# ProProject__CW32__2024-03-03.net
KiCad netlist of a schematic drawn in EasyEDA Pro
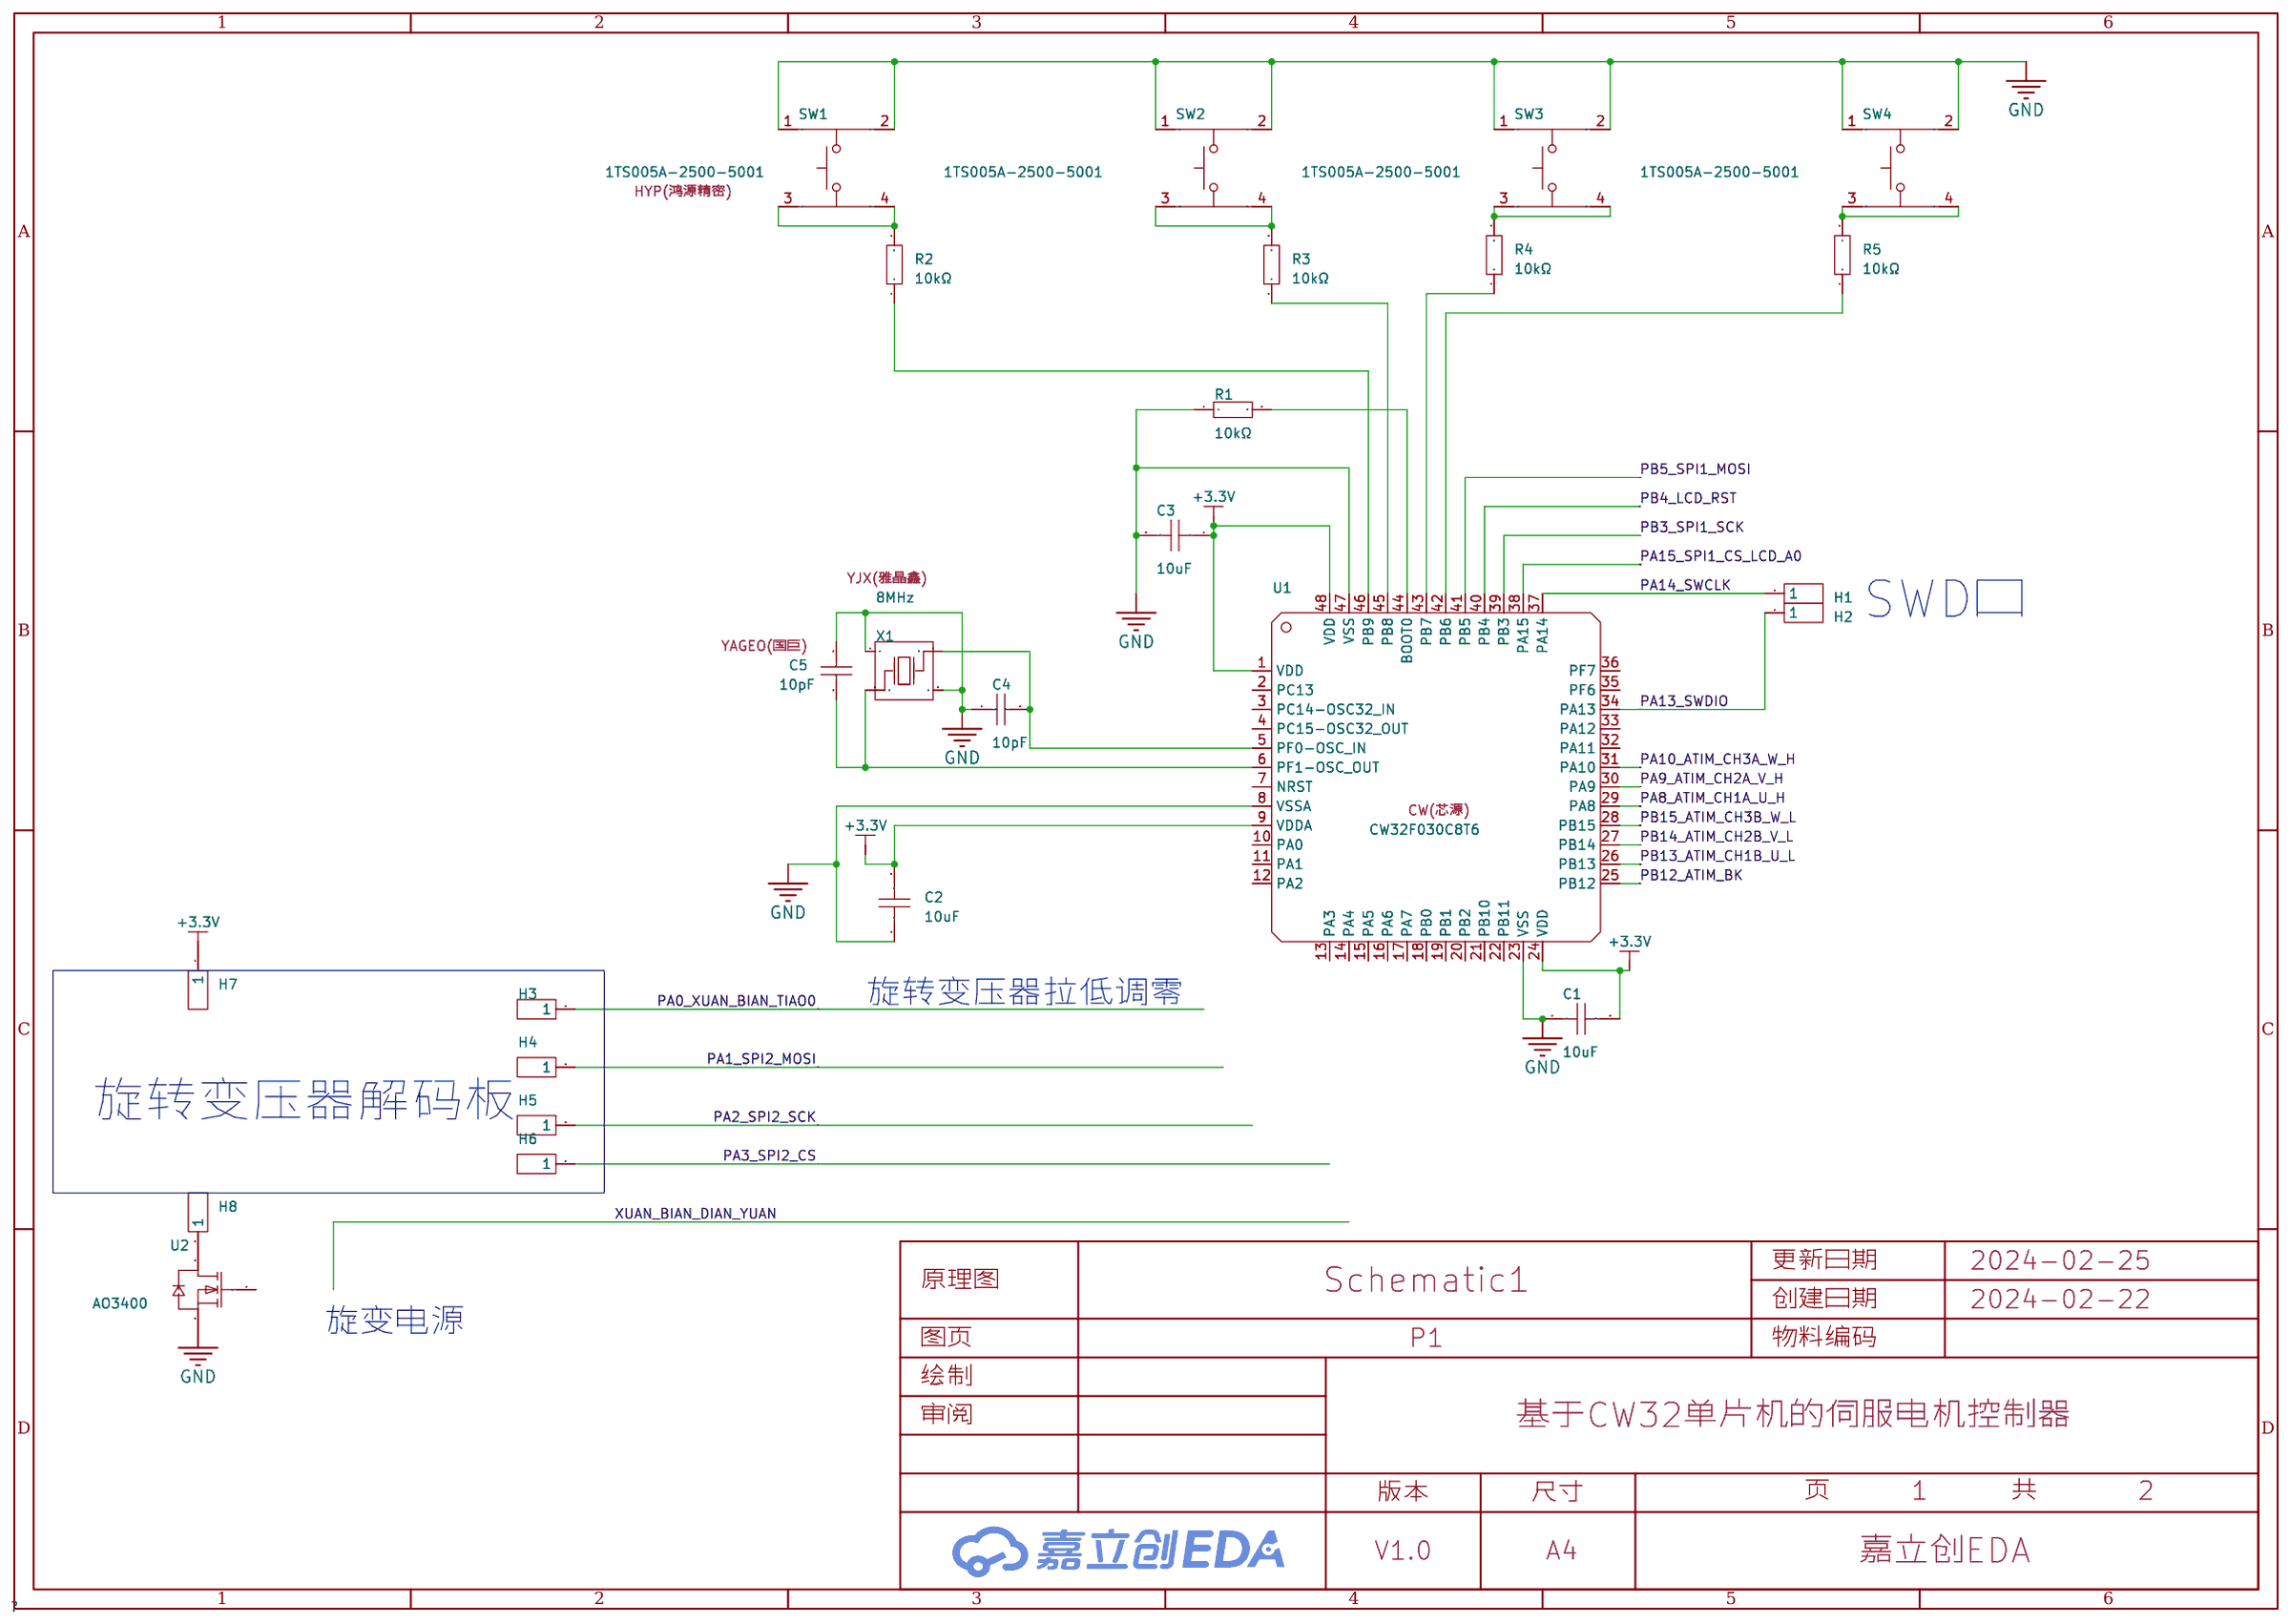
[diagram p0: P1]
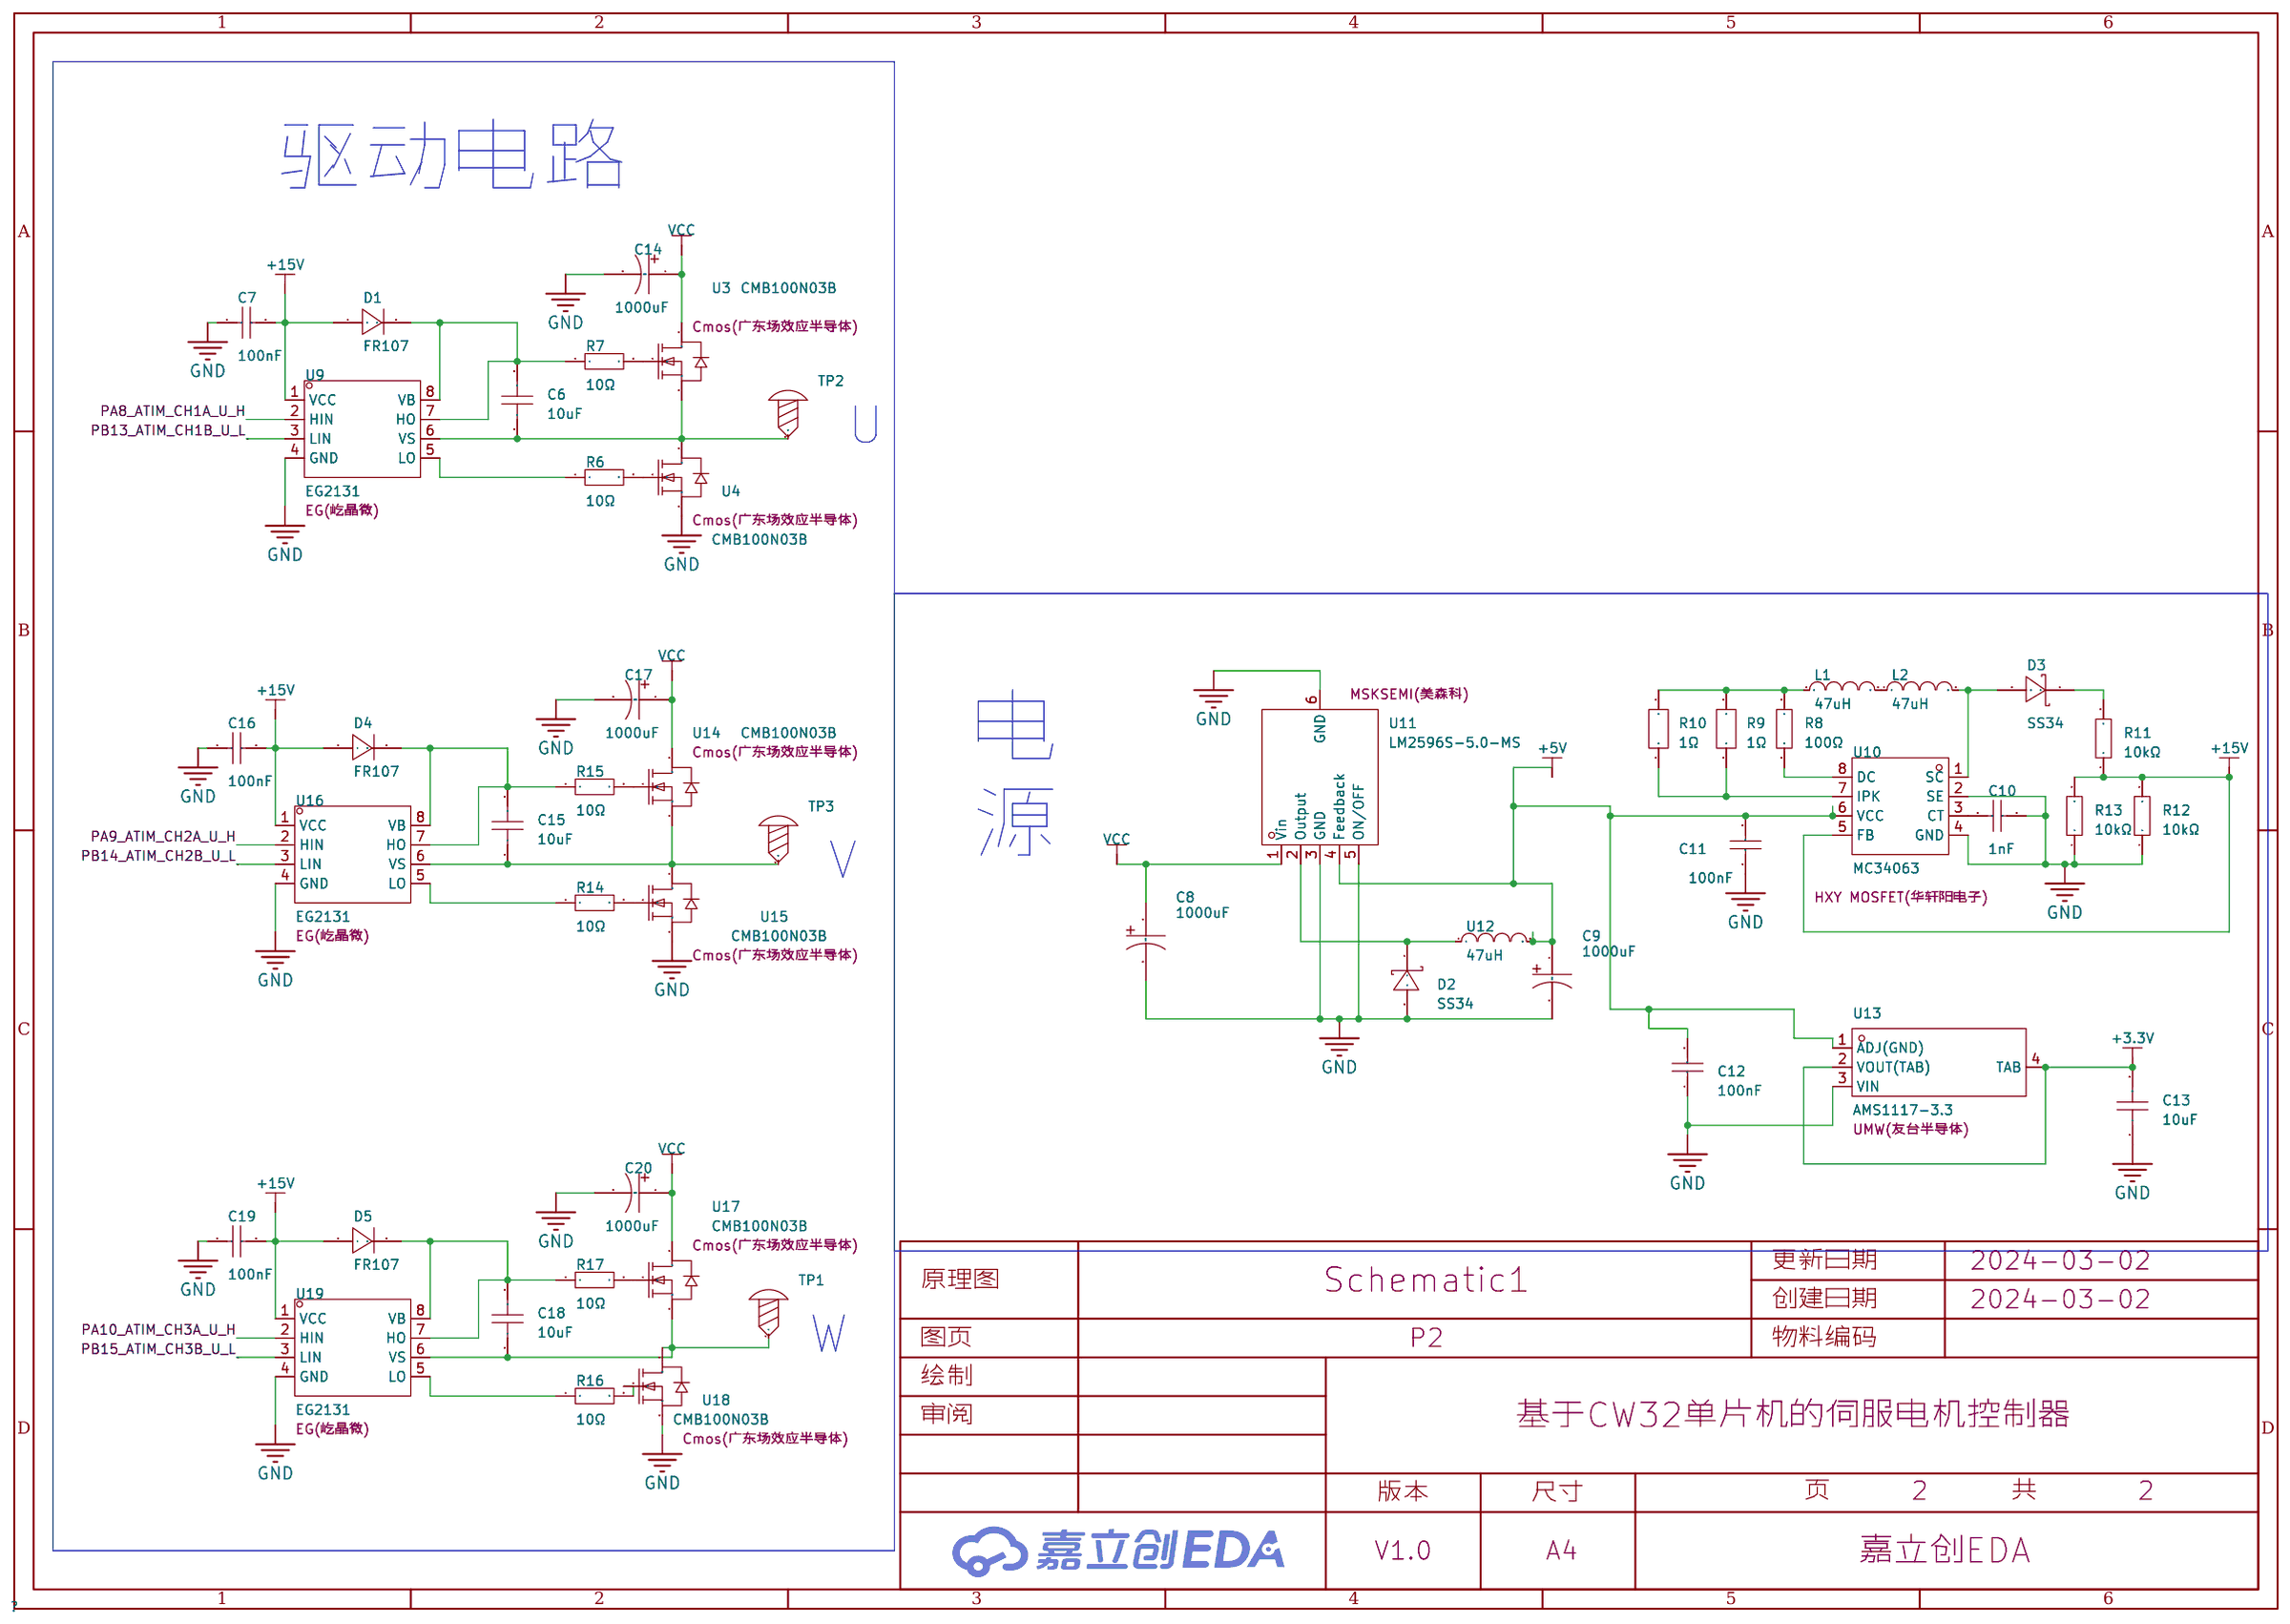
[diagram p1: P2]

(export (version "E")
  (design (tool "Eeschema 10.0.6"))
  (components
    (comp (ref "C1")
      (value "10uF")
      (footprint "easyedapro:C0603")
      (description "容值:10uF;精度:±10%;额定电压:10V;材质(温度系数):X5R;")
      (fields
        (field (name "Manufacturer Part") "CL10A106KP8NNNC")
        (field (name "Manufacturer") "SAMSUNG(三星)")
      )
      (libsource (lib "easyedapro") (part "CL10A106KP8NNNC"))
    )
    (comp (ref "C2")
      (value "10uF")
      (footprint "easyedapro:C0603")
      (description "容值:10uF;精度:±10%;额定电压:10V;材质(温度系数):X5R;")
      (fields
        (field (name "Manufacturer Part") "CL10A106KP8NNNC")
        (field (name "Manufacturer") "SAMSUNG(三星)")
      )
      (libsource (lib "easyedapro") (part "CL10A106KP8NNNC"))
    )
    (comp (ref "C3")
      (value "10uF")
      (footprint "easyedapro:C0603")
      (description "容值:10uF;精度:±10%;额定电压:10V;材质(温度系数):X5R;")
      (fields
        (field (name "Manufacturer Part") "CL10A106KP8NNNC")
        (field (name "Manufacturer") "SAMSUNG(三星)")
      )
      (libsource (lib "easyedapro") (part "CL10A106KP8NNNC"))
    )
    (comp (ref "C4")
      (value "10pF")
      (footprint "easyedapro:C0603")
      (description "容值:10pF;精度:±5%;额定电压:50V;材质(温度系数):NP0;")
      (fields
        (field (name "Manufacturer Part") "CC0603JRNPO9BN100")
        (field (name "Manufacturer") "YAGEO(国巨)")
      )
      (libsource (lib "easyedapro") (part "CC0603JRNPO9BN100"))
    )
    (comp (ref "C5")
      (value "10pF")
      (footprint "easyedapro:C0603")
      (description "容值:10pF;精度:±5%;额定电压:50V;材质(温度系数):NP0;")
      (fields
        (field (name "Manufacturer Part") "CC0603JRNPO9BN100")
        (field (name "Manufacturer") "YAGEO(国巨)")
      )
      (libsource (lib "easyedapro") (part "CC0603JRNPO9BN100"))
    )
    (comp (ref "H1")
      (value "~")
      (footprint "easyedapro:HDR-TH_1P-V-M_XKB_X4611WV-01I-C28D40")
      (libsource (lib "easyedapro") (part "HDR_1x1"))
    )
    (comp (ref "H2")
      (value "~")
      (footprint "easyedapro:HDR-TH_1P-V-M_XKB_X4611WV-01I-C28D40")
      (libsource (lib "easyedapro") (part "HDR_1x1"))
    )
    (comp (ref "H3")
      (value "~")
      (footprint "easyedapro:HDR-TH_1P-V-M_XKB_X4611WV-01I-C28D40")
      (libsource (lib "easyedapro") (part "HDR_1x1"))
    )
    (comp (ref "H4")
      (value "~")
      (footprint "easyedapro:HDR-TH_1P-V-M_XKB_X4611WV-01I-C28D40")
      (libsource (lib "easyedapro") (part "HDR_1x1"))
    )
    (comp (ref "H5")
      (value "~")
      (footprint "easyedapro:HDR-TH_1P-V-M_XKB_X4611WV-01I-C28D40")
      (libsource (lib "easyedapro") (part "HDR_1x1"))
    )
    (comp (ref "H6")
      (value "~")
      (footprint "easyedapro:HDR-TH_1P-V-M_XKB_X4611WV-01I-C28D40")
      (libsource (lib "easyedapro") (part "HDR_1x1"))
    )
    (comp (ref "H7")
      (value "~")
      (footprint "easyedapro:HDR-TH_1P-V-M_XKB_X4611WV-01I-C28D40")
      (libsource (lib "easyedapro") (part "HDR_1x1"))
    )
    (comp (ref "H8")
      (value "~")
      (footprint "easyedapro:HDR-TH_1P-V-M_XKB_X4611WV-01I-C28D40")
      (libsource (lib "easyedapro") (part "HDR_1x1"))
    )
    (comp (ref "R1")
      (value "10kΩ")
      (footprint "easyedapro:R0603")
      (description "电阻类型:厚膜电阻;阻值:10kΩ;精度:±1%;功率:100mW;最大工作电压:75V;温度系数:±100ppm/°C;")
      (fields (field (name "Manufacturer Part") "RC0603FR-0710KL") (field (name "Manufacturer") "YAGEO(国巨)"))
      (libsource (lib "easyedapro") (part "RC0603FR-0710KL"))
    )
    (comp (ref "R2")
      (value "10kΩ")
      (footprint "easyedapro:R0603")
      (description "电阻类型:厚膜电阻;阻值:10kΩ;精度:±1%;功率:100mW;最大工作电压:75V;温度系数:±100ppm/°C;")
      (fields (field (name "Manufacturer Part") "RC0603FR-0710KL") (field (name "Manufacturer") "YAGEO(国巨)"))
      (libsource (lib "easyedapro") (part "RC0603FR-0710KL"))
    )
    (comp (ref "R3")
      (value "10kΩ")
      (footprint "easyedapro:R0603")
      (description "电阻类型:厚膜电阻;阻值:10kΩ;精度:±1%;功率:100mW;最大工作电压:75V;温度系数:±100ppm/°C;")
      (fields (field (name "Manufacturer Part") "RC0603FR-0710KL") (field (name "Manufacturer") "YAGEO(国巨)"))
      (libsource (lib "easyedapro") (part "RC0603FR-0710KL"))
    )
    (comp (ref "R4")
      (value "10kΩ")
      (footprint "easyedapro:R0603")
      (description "电阻类型:厚膜电阻;阻值:10kΩ;精度:±1%;功率:100mW;最大工作电压:75V;温度系数:±100ppm/°C;")
      (fields (field (name "Manufacturer Part") "RC0603FR-0710KL") (field (name "Manufacturer") "YAGEO(国巨)"))
      (libsource (lib "easyedapro") (part "RC0603FR-0710KL"))
    )
    (comp (ref "R5")
      (value "10kΩ")
      (footprint "easyedapro:R0603")
      (description "电阻类型:厚膜电阻;阻值:10kΩ;精度:±1%;功率:100mW;最大工作电压:75V;温度系数:±100ppm/°C;")
      (fields (field (name "Manufacturer Part") "RC0603FR-0710KL") (field (name "Manufacturer") "YAGEO(国巨)"))
      (libsource (lib "easyedapro") (part "RC0603FR-0710KL"))
    )
    (comp (ref "SW1")
      (value "1TS005A-2500-5001")
      (footprint "easyedapro:SW-TH_4P-L6.0-W6.0-P3.90-LS6.5")
      (fields (field (name "Manufacturer") "HYP(鸿源精密)"))
      (libsource (lib "easyedapro") (part "1TS005A-2500-5001"))
    )
    (comp (ref "SW2")
      (value "1TS005A-2500-5001")
      (footprint "easyedapro:SW-TH_4P-L6.0-W6.0-P3.90-LS6.5")
      (fields (field (name "Manufacturer") "HYP(鸿源精密)"))
      (libsource (lib "easyedapro") (part "1TS005A-2500-5001"))
    )
    (comp (ref "SW3")
      (value "1TS005A-2500-5001")
      (footprint "easyedapro:SW-TH_4P-L6.0-W6.0-P3.90-LS6.5")
      (fields (field (name "Manufacturer") "HYP(鸿源精密)"))
      (libsource (lib "easyedapro") (part "1TS005A-2500-5001"))
    )
    (comp (ref "SW4")
      (value "1TS005A-2500-5001")
      (footprint "easyedapro:SW-TH_4P-L6.0-W6.0-P3.90-LS6.5")
      (fields (field (name "Manufacturer") "HYP(鸿源精密)"))
      (libsource (lib "easyedapro") (part "1TS005A-2500-5001"))
    )
    (comp (ref "U1")
      (value "CW32F030C8T6")
      (footprint "easyedapro:LQFP-48_L7.0-W7.0-P0.50-LS9.0-TL")
      (description "CPU内核:ARM-M系列;RAM总容量:8KB;GPIO端口数量:39;工作电压范围:1.65V~5.5V;CPU最大主频:64MHz;程序存储器类型:-;")
      (fields (field (name "Manufacturer") "CW(芯源)"))
      (libsource (lib "easyedapro") (part "CW32F030C8T6_C3019113"))
    )
    (comp (ref "U2")
      (value "AO3400")
      (footprint "easyedapro:SOT-23-3_L2.9-W1.3-P0.95-LS2.4-BR")
      (fields (field (name "Manufacturer") "ElecSuper(静芯微)"))
      (libsource (lib "easyedapro") (part "AO3400_C5224189"))
    )
    (comp (ref "X1")
      (value "8MHz")
      (footprint "easyedapro:OSC-SMD_4P-L3.2-W2.5-BL")
      (description "晶振类型:贴片晶振;频率:8MHz;常温频差:±10ppm;外接负载电容:10pF;频率稳定度(全温):±15ppm;")
      (fields (field (name "Manufacturer Part") "TAXM8M4RDBCCT2T") (field (name "Manufacturer") "YJX(雅晶鑫)"))
      (libsource (lib "easyedapro") (part "TAXM8M4RDBCCT2T"))
    )
    (comp (ref "C6")
      (value "10uF")
      (footprint "easyedapro:C0805")
      (description "容值:10uF;精度:±10%;额定电压:25V;材质(温度系数):X5R;")
      (fields
        (field (name "Manufacturer Part") "CL21A106KAYNNNE")
        (field (name "Manufacturer") "SAMSUNG(三星)")
      )
      (libsource (lib "easyedapro") (part "CL21A106KAYNNNE"))
    )
    (comp (ref "C7")
      (value "100nF")
      (footprint "easyedapro:C0603")
      (description "容值:100nF;精度:±10%;额定电压:50V;材质(温度系数):X7R;")
      (fields (field (name "Manufacturer Part") "0603B104K500NT") (field (name "Manufacturer") "FH(风华)"))
      (libsource (lib "easyedapro") (part "0603B104K500NT"))
    )
    (comp (ref "C8")
      (value "1000uF")
      (footprint "easyedapro:CAP-TH_BD10.0-P5.00-D1.0-FD")
      (description "容值:1000uF;精度:±20%;额定电压:35V;")
      (fields (field (name "Manufacturer Part") "ERR1VM102G20OT") (field (name "Manufacturer") "AISHI(艾华集团)"))
      (libsource (lib "easyedapro") (part "ERR1VM102G20OT"))
    )
    (comp (ref "C9")
      (value "1000uF")
      (footprint "easyedapro:CAP-TH_BD10.0-P5.00-D1.0-FD")
      (description "容值:1000uF;精度:±20%;额定电压:35V;")
      (fields (field (name "Manufacturer Part") "ERR1VM102G20OT") (field (name "Manufacturer") "AISHI(艾华集团)"))
      (libsource (lib "easyedapro") (part "ERR1VM102G20OT"))
    )
    (comp (ref "C10")
      (value "1nF")
      (footprint "easyedapro:C0603")
      (description "容值:1nF;精度:±5%;额定电压:50V;材质(温度系数):NP0;")
      (fields
        (field (name "Manufacturer Part") "CC0603JRNPO9BN102")
        (field (name "Manufacturer") "YAGEO(国巨)")
      )
      (libsource (lib "easyedapro") (part "CC0603JRNPO9BN102"))
    )
    (comp (ref "C11")
      (value "100nF")
      (footprint "easyedapro:C0603")
      (description "容值:100nF;精度:±10%;额定电压:50V;材质(温度系数):X7R;")
      (fields (field (name "Manufacturer Part") "0603B104K500NT") (field (name "Manufacturer") "FH(风华)"))
      (libsource (lib "easyedapro") (part "0603B104K500NT"))
    )
    (comp (ref "C12")
      (value "100nF")
      (footprint "easyedapro:C0603")
      (description "容值:100nF;精度:±10%;额定电压:50V;材质(温度系数):X7R;")
      (fields (field (name "Manufacturer Part") "0603B104K500NT") (field (name "Manufacturer") "FH(风华)"))
      (libsource (lib "easyedapro") (part "0603B104K500NT"))
    )
    (comp (ref "C13")
      (value "10uF")
      (footprint "easyedapro:C0603")
      (description "容值:10uF;精度:±10%;额定电压:10V;材质(温度系数):X5R;")
      (fields
        (field (name "Manufacturer Part") "CL10A106KP8NNNC")
        (field (name "Manufacturer") "SAMSUNG(三星)")
      )
      (libsource (lib "easyedapro") (part "CL10A106KP8NNNC"))
    )
    (comp (ref "C14")
      (value "1000uF")
      (footprint "easyedapro:CAP-TH_BD10.0-P5.00-D1.0-FD")
      (description "容值:1000uF;精度:±20%;额定电压:35V;")
      (fields (field (name "Manufacturer Part") "ERR1VM102G20OT") (field (name "Manufacturer") "AISHI(艾华集团)"))
      (libsource (lib "easyedapro") (part "ERR1VM102G20OT"))
    )
    (comp (ref "C15")
      (value "10uF")
      (footprint "easyedapro:C0805")
      (description "容值:10uF;精度:±10%;额定电压:25V;材质(温度系数):X5R;")
      (fields
        (field (name "Manufacturer Part") "CL21A106KAYNNNE")
        (field (name "Manufacturer") "SAMSUNG(三星)")
      )
      (libsource (lib "easyedapro") (part "CL21A106KAYNNNE"))
    )
    (comp (ref "C16")
      (value "100nF")
      (footprint "easyedapro:C0603")
      (description "容值:100nF;精度:±10%;额定电压:50V;材质(温度系数):X7R;")
      (fields (field (name "Manufacturer Part") "0603B104K500NT") (field (name "Manufacturer") "FH(风华)"))
      (libsource (lib "easyedapro") (part "0603B104K500NT"))
    )
    (comp (ref "C17")
      (value "1000uF")
      (footprint "easyedapro:CAP-TH_BD10.0-P5.00-D1.0-FD")
      (description "容值:1000uF;精度:±20%;额定电压:35V;")
      (fields (field (name "Manufacturer Part") "ERR1VM102G20OT") (field (name "Manufacturer") "AISHI(艾华集团)"))
      (libsource (lib "easyedapro") (part "ERR1VM102G20OT"))
    )
    (comp (ref "C18")
      (value "10uF")
      (footprint "easyedapro:C0805")
      (description "容值:10uF;精度:±10%;额定电压:25V;材质(温度系数):X5R;")
      (fields
        (field (name "Manufacturer Part") "CL21A106KAYNNNE")
        (field (name "Manufacturer") "SAMSUNG(三星)")
      )
      (libsource (lib "easyedapro") (part "CL21A106KAYNNNE"))
    )
    (comp (ref "C19")
      (value "100nF")
      (footprint "easyedapro:C0603")
      (description "容值:100nF;精度:±10%;额定电压:50V;材质(温度系数):X7R;")
      (fields (field (name "Manufacturer Part") "0603B104K500NT") (field (name "Manufacturer") "FH(风华)"))
      (libsource (lib "easyedapro") (part "0603B104K500NT"))
    )
    (comp (ref "C20")
      (value "1000uF")
      (footprint "easyedapro:CAP-TH_BD10.0-P5.00-D1.0-FD")
      (description "容值:1000uF;精度:±20%;额定电压:35V;")
      (fields (field (name "Manufacturer Part") "ERR1VM102G20OT") (field (name "Manufacturer") "AISHI(艾华集团)"))
      (libsource (lib "easyedapro") (part "ERR1VM102G20OT"))
    )
    (comp (ref "D1")
      (value "FR107")
      (footprint "easyedapro:DO-41_BD2.4-L4.7-P8.70-D0.9-FD")
      (description "二极管配置:-;正向压降(Vf):1.3V@1A;直流反向耐压(Vr):1kV;平均整流电流(Io):1A;反向恢复时间(trr):500ns;")
      (fields (field (name "Manufacturer") "MDD"))
      (libsource (lib "easyedapro") (part "FR107_C35253"))
    )
    (comp (ref "D2")
      (value "SS34")
      (footprint "easyedapro:SMA_L4.3-W2.6-LS5.2-RD")
      (description "二极管配置:独立式;正向压降(Vf):550mV@3A;直流反向耐压(Vr):40V;平均整流电流(Io):3A;")
      (fields (field (name "Manufacturer") "MDD"))
      (libsource (lib "easyedapro") (part "SS34_C8678"))
    )
    (comp (ref "D3")
      (value "SS34")
      (footprint "easyedapro:SMA_L4.3-W2.6-LS5.2-RD")
      (description "二极管配置:独立式;正向压降(Vf):550mV@3A;直流反向耐压(Vr):40V;平均整流电流(Io):3A;")
      (fields (field (name "Manufacturer") "MDD"))
      (libsource (lib "easyedapro") (part "SS34_C8678"))
    )
    (comp (ref "D4")
      (value "FR107")
      (footprint "easyedapro:DO-41_BD2.4-L4.7-P8.70-D0.9-FD")
      (description "二极管配置:-;正向压降(Vf):1.3V@1A;直流反向耐压(Vr):1kV;平均整流电流(Io):1A;反向恢复时间(trr):500ns;")
      (fields (field (name "Manufacturer") "MDD"))
      (libsource (lib "easyedapro") (part "FR107_C35253"))
    )
    (comp (ref "D5")
      (value "FR107")
      (footprint "easyedapro:DO-41_BD2.4-L4.7-P8.70-D0.9-FD")
      (description "二极管配置:-;正向压降(Vf):1.3V@1A;直流反向耐压(Vr):1kV;平均整流电流(Io):1A;反向恢复时间(trr):500ns;")
      (fields (field (name "Manufacturer") "MDD"))
      (libsource (lib "easyedapro") (part "FR107_C35253"))
    )
    (comp (ref "L1")
      (value "47uH")
      (footprint "easyedapro:IND-SMD_L4.5-W4.0_SLF0403")
      (description "电感值:47uH;精度:±10%;额定电流:540mA;")
      (fields
        (field (name "Manufacturer Part") "SLF0403-470KTT")
        (field (name "Manufacturer") "Sunltech(韩国顺磁)")
      )
      (libsource (lib "easyedapro") (part "SLF0403-470KTT"))
    )
    (comp (ref "L2")
      (value "47uH")
      (footprint "easyedapro:IND-SMD_L4.5-W4.0_SLF0403")
      (description "电感值:47uH;精度:±10%;额定电流:540mA;")
      (fields
        (field (name "Manufacturer Part") "SLF0403-470KTT")
        (field (name "Manufacturer") "Sunltech(韩国顺磁)")
      )
      (libsource (lib "easyedapro") (part "SLF0403-470KTT"))
    )
    (comp (ref "R6")
      (value "10Ω")
      (footprint "easyedapro:R0603")
      (description "电阻类型:厚膜电阻;阻值:10Ω;精度:±1%;功率:100mW;最大工作电压:75V;温度系数:±400ppm/°C;")
      (fields
        (field (name "Manufacturer Part") "0603WAF100JT5E")
        (field (name "Manufacturer") "UNI-ROYAL(厚声)")
      )
      (libsource (lib "easyedapro") (part "0603WAF100JT5E"))
    )
    (comp (ref "R7")
      (value "10Ω")
      (footprint "easyedapro:R0603")
      (description "电阻类型:厚膜电阻;阻值:10Ω;精度:±1%;功率:100mW;最大工作电压:75V;温度系数:±400ppm/°C;")
      (fields
        (field (name "Manufacturer Part") "0603WAF100JT5E")
        (field (name "Manufacturer") "UNI-ROYAL(厚声)")
      )
      (libsource (lib "easyedapro") (part "0603WAF100JT5E"))
    )
    (comp (ref "R8")
      (value "100Ω")
      (footprint "easyedapro:R0603")
      (description "电阻类型:厚膜电阻;阻值:100Ω;精度:±1%;功率:100mW;最大工作电压:75V;温度系数:±100ppm/°C;")
      (fields (field (name "Manufacturer Part") "RC0603FR-07100RL") (field (name "Manufacturer") "YAGEO(国巨)"))
      (libsource (lib "easyedapro") (part "RC0603FR-07100RL"))
    )
    (comp (ref "R9")
      (value "1Ω")
      (footprint "easyedapro:R0603")
      (description "电阻类型:厚膜电阻;阻值:1Ω;精度:±1%;功率:100mW;最大工作电压:75V;")
      (fields (field (name "Manufacturer Part") "SCR0603F1R") (field (name "Manufacturer") "VO(翔胜)"))
      (libsource (lib "easyedapro") (part "SCR0603F1R"))
    )
    (comp (ref "R10")
      (value "1Ω")
      (footprint "easyedapro:R0603")
      (description "电阻类型:厚膜电阻;阻值:1Ω;精度:±1%;功率:100mW;最大工作电压:75V;")
      (fields (field (name "Manufacturer Part") "SCR0603F1R") (field (name "Manufacturer") "VO(翔胜)"))
      (libsource (lib "easyedapro") (part "SCR0603F1R"))
    )
    (comp (ref "R11")
      (value "10kΩ")
      (footprint "easyedapro:R0603")
      (description "电阻类型:厚膜电阻;阻值:10kΩ;精度:±1%;功率:100mW;最大工作电压:75V;温度系数:±100ppm/°C;")
      (fields (field (name "Manufacturer Part") "RC0603FR-0710KL") (field (name "Manufacturer") "YAGEO(国巨)"))
      (libsource (lib "easyedapro") (part "RC0603FR-0710KL"))
    )
    (comp (ref "R12")
      (value "10kΩ")
      (footprint "easyedapro:R0603")
      (description "电阻类型:厚膜电阻;阻值:10kΩ;精度:±1%;功率:100mW;最大工作电压:75V;温度系数:±100ppm/°C;")
      (fields (field (name "Manufacturer Part") "RC0603FR-0710KL") (field (name "Manufacturer") "YAGEO(国巨)"))
      (libsource (lib "easyedapro") (part "RC0603FR-0710KL"))
    )
    (comp (ref "R13")
      (value "10kΩ")
      (footprint "easyedapro:R0603")
      (description "电阻类型:厚膜电阻;阻值:10kΩ;精度:±1%;功率:100mW;最大工作电压:75V;温度系数:±100ppm/°C;")
      (fields (field (name "Manufacturer Part") "RC0603FR-0710KL") (field (name "Manufacturer") "YAGEO(国巨)"))
      (libsource (lib "easyedapro") (part "RC0603FR-0710KL"))
    )
    (comp (ref "R14")
      (value "10Ω")
      (footprint "easyedapro:R0603")
      (description "电阻类型:厚膜电阻;阻值:10Ω;精度:±1%;功率:100mW;最大工作电压:75V;温度系数:±400ppm/°C;")
      (fields
        (field (name "Manufacturer Part") "0603WAF100JT5E")
        (field (name "Manufacturer") "UNI-ROYAL(厚声)")
      )
      (libsource (lib "easyedapro") (part "0603WAF100JT5E"))
    )
    (comp (ref "R15")
      (value "10Ω")
      (footprint "easyedapro:R0603")
      (description "电阻类型:厚膜电阻;阻值:10Ω;精度:±1%;功率:100mW;最大工作电压:75V;温度系数:±400ppm/°C;")
      (fields
        (field (name "Manufacturer Part") "0603WAF100JT5E")
        (field (name "Manufacturer") "UNI-ROYAL(厚声)")
      )
      (libsource (lib "easyedapro") (part "0603WAF100JT5E"))
    )
    (comp (ref "R16")
      (value "10Ω")
      (footprint "easyedapro:R0603")
      (description "电阻类型:厚膜电阻;阻值:10Ω;精度:±1%;功率:100mW;最大工作电压:75V;温度系数:±400ppm/°C;")
      (fields
        (field (name "Manufacturer Part") "0603WAF100JT5E")
        (field (name "Manufacturer") "UNI-ROYAL(厚声)")
      )
      (libsource (lib "easyedapro") (part "0603WAF100JT5E"))
    )
    (comp (ref "R17")
      (value "10Ω")
      (footprint "easyedapro:R0603")
      (description "电阻类型:厚膜电阻;阻值:10Ω;精度:±1%;功率:100mW;最大工作电压:75V;温度系数:±400ppm/°C;")
      (fields
        (field (name "Manufacturer Part") "0603WAF100JT5E")
        (field (name "Manufacturer") "UNI-ROYAL(厚声)")
      )
      (libsource (lib "easyedapro") (part "0603WAF100JT5E"))
    )
    (comp (ref "TP1") (value "~") (footprint "easyedapro:M4螺丝") (libsource (lib "easyedapro") (part "螺丝孔")))
    (comp (ref "TP2") (value "~") (footprint "easyedapro:M4螺丝") (libsource (lib "easyedapro") (part "螺丝孔")))
    (comp (ref "TP3") (value "~") (footprint "easyedapro:M4螺丝") (libsource (lib "easyedapro") (part "螺丝孔")))
    (comp (ref "U3")
      (value "CMB100N03B")
      (footprint "easyedapro:TO-263-2_L10.1-W9.1-P5.08-LS15.2-BR")
      (description "类型:N沟道;漏源电压(Vdss):30V;连续漏极电流(Id):100A;功率(Pd):300W;导通电阻(RDS(on)@Vgs,Id):4.5mΩ;")
      (fields (field (name "Manufacturer") "Cmos(广东场效应半导体)"))
      (libsource (lib "easyedapro") (part "CMB100N03B"))
    )
    (comp (ref "U4")
      (value "CMB100N03B")
      (footprint "easyedapro:TO-263-2_L10.1-W9.1-P5.08-LS15.2-BR")
      (description "类型:N沟道;漏源电压(Vdss):30V;连续漏极电流(Id):100A;功率(Pd):300W;导通电阻(RDS(on)@Vgs,Id):4.5mΩ;")
      (fields (field (name "Manufacturer") "Cmos(广东场效应半导体)"))
      (libsource (lib "easyedapro") (part "CMB100N03B"))
    )
    (comp (ref "U9")
      (value "EG2131")
      (footprint "easyedapro:SOIC-8_L5.0-W4.0-P1.27-LS6.0-BL")
      (fields (field (name "Manufacturer") "EG(屹晶微)"))
      (libsource (lib "easyedapro") (part "EG2131"))
    )
    (comp (ref "U10")
      (value "MC34063")
      (footprint "easyedapro:SOIC-8_L5.0-W4.0-P1.27-LS6.0-BL")
      (description "功能类型:升降压型;输出类型:可调;输入电压:3V~40V;输出电压:1.25V~40V;输出电流(最大值):1.3A;")
      (fields (field (name "Manufacturer") "HXY MOSFET(华轩阳电子)"))
      (libsource (lib "easyedapro") (part "MC34063_C5349988"))
    )
    (comp (ref "U11")
      (value "LM2596S-5.0-MS")
      (footprint "easyedapro:TO-263-5_L10.0-W8.4-P1.70-LS15.3-BR")
      (description "功能类型:降压型;输出类型:-;输入电压:7V~40V;输出电压:5V;输出电流(最大值):3A;")
      (fields (field (name "Manufacturer") "MSKSEMI(美森科)"))
      (libsource (lib "easyedapro") (part "LM2596S-5.0_C5174628"))
    )
    (comp (ref "U12")
      (value "47uH")
      (footprint "easyedapro:IND-SMD_L7.1-W6.6")
      (description "电感值:47uH;精度:±20%;额定电流:1.25A;饱和电流(Isat):1.66A;类型:一体成型电感;")
      (fields (field (name "Manufacturer Part") "APH0630T470M") (field (name "Manufacturer") "APV(爱普微)"))
      (libsource (lib "easyedapro") (part "APH0630T470M"))
    )
    (comp (ref "U13")
      (value "AMS1117-3.3")
      (footprint "easyedapro:SOT-223-4_L6.5-W3.5-P2.30-LS7.0-BR")
      (description "输出类型:固定;最大输入电压:12V;输出电压:3.3V;最大输出电流:1A;电源纹波抑制比(PSRR):60dB@(120Hz);输出极性:正极;")
      (fields (field (name "Manufacturer") "UMW(友台半导体)"))
      (libsource (lib "easyedapro") (part "AMS1117-3.3_C347222"))
    )
    (comp (ref "U14")
      (value "CMB100N03B")
      (footprint "easyedapro:TO-263-2_L10.1-W9.1-P5.08-LS15.2-BR")
      (description "类型:N沟道;漏源电压(Vdss):30V;连续漏极电流(Id):100A;功率(Pd):300W;导通电阻(RDS(on)@Vgs,Id):4.5mΩ;")
      (fields (field (name "Manufacturer") "Cmos(广东场效应半导体)"))
      (libsource (lib "easyedapro") (part "CMB100N03B"))
    )
    (comp (ref "U15")
      (value "CMB100N03B")
      (footprint "easyedapro:TO-263-2_L10.1-W9.1-P5.08-LS15.2-BR")
      (description "类型:N沟道;漏源电压(Vdss):30V;连续漏极电流(Id):100A;功率(Pd):300W;导通电阻(RDS(on)@Vgs,Id):4.5mΩ;")
      (fields (field (name "Manufacturer") "Cmos(广东场效应半导体)"))
      (libsource (lib "easyedapro") (part "CMB100N03B"))
    )
    (comp (ref "U16")
      (value "EG2131")
      (footprint "easyedapro:SOIC-8_L5.0-W4.0-P1.27-LS6.0-BL")
      (fields (field (name "Manufacturer") "EG(屹晶微)"))
      (libsource (lib "easyedapro") (part "EG2131"))
    )
    (comp (ref "U17")
      (value "CMB100N03B")
      (footprint "easyedapro:TO-263-2_L10.1-W9.1-P5.08-LS15.2-BR")
      (description "类型:N沟道;漏源电压(Vdss):30V;连续漏极电流(Id):100A;功率(Pd):300W;导通电阻(RDS(on)@Vgs,Id):4.5mΩ;")
      (fields (field (name "Manufacturer") "Cmos(广东场效应半导体)"))
      (libsource (lib "easyedapro") (part "CMB100N03B"))
    )
    (comp (ref "U18")
      (value "CMB100N03B")
      (footprint "easyedapro:TO-263-2_L10.1-W9.1-P5.08-LS15.2-BR")
      (description "类型:N沟道;漏源电压(Vdss):30V;连续漏极电流(Id):100A;功率(Pd):300W;导通电阻(RDS(on)@Vgs,Id):4.5mΩ;")
      (fields (field (name "Manufacturer") "Cmos(广东场效应半导体)"))
      (libsource (lib "easyedapro") (part "CMB100N03B"))
    )
    (comp (ref "U19")
      (value "EG2131")
      (footprint "easyedapro:SOIC-8_L5.0-W4.0-P1.27-LS6.0-BL")
      (fields (field (name "Manufacturer") "EG(屹晶微)"))
      (libsource (lib "easyedapro") (part "EG2131"))
    )
  )
  (nets
    (net (code "1") (name "+3.3V") (class "Default")
      (node (ref "C1") (pin "2") (pinfunction "2_2") (pintype "unspecified"))
      (node (ref "C13") (pin "2") (pinfunction "2_2") (pintype "unspecified"))
      (node (ref "C2") (pin "2") (pinfunction "2_2") (pintype "unspecified"))
      (node (ref "C3") (pin "1") (pinfunction "1_1") (pintype "unspecified"))
      (node (ref "H7") (pin "1") (pinfunction "1_1") (pintype "unspecified"))
      (node (ref "U1") (pin "1") (pinfunction "VDD_1") (pintype "unspecified"))
      (node (ref "U1") (pin "24") (pinfunction "VDD_24") (pintype "unspecified"))
      (node (ref "U1") (pin "48") (pinfunction "VDD_48") (pintype "unspecified"))
      (node (ref "U1") (pin "9") (pinfunction "VDDA_9") (pintype "unspecified"))
      (node (ref "U13") (pin "2") (pinfunction "VOUT(TAB)_2") (pintype "unspecified"))
      (node (ref "U13") (pin "4") (pinfunction "TAB_4") (pintype "unspecified"))
    )
    (net (code "2") (name "+5V") (class "Default")
      (node (ref "C11") (pin "2") (pinfunction "2_2") (pintype "input"))
      (node (ref "C12") (pin "2") (pinfunction "2_2") (pintype "input"))
      (node (ref "C9") (pin "1") (pinfunction "1_1") (pintype "input"))
      (node (ref "U10") (pin "6") (pinfunction "VCC_6") (pintype "unspecified"))
      (node (ref "U11") (pin "4") (pinfunction "Feedback_4") (pintype "unspecified"))
      (node (ref "U12") (pin "2") (pinfunction "2_2") (pintype "unspecified"))
      (node (ref "U13") (pin "1") (pinfunction "ADJ(GND)_1") (pintype "unspecified"))
    )
    (net (code "3") (name "+15V") (class "Default")
      (node (ref "C16") (pin "2") (pinfunction "2_2") (pintype "input"))
      (node (ref "C19") (pin "2") (pinfunction "2_2") (pintype "input"))
      (node (ref "C7") (pin "2") (pinfunction "2_2") (pintype "input"))
      (node (ref "D1") (pin "1") (pinfunction "A_1") (pintype "unspecified"))
      (node (ref "D4") (pin "1") (pinfunction "A_1") (pintype "unspecified"))
      (node (ref "D5") (pin "1") (pinfunction "A_1") (pintype "unspecified"))
      (node (ref "R11") (pin "1") (pinfunction "1_1") (pintype "input"))
      (node (ref "R12") (pin "2") (pinfunction "2_2") (pintype "input"))
      (node (ref "R13") (pin "2") (pinfunction "2_2") (pintype "input"))
      (node (ref "U10") (pin "5") (pinfunction "FB_5") (pintype "unspecified"))
      (node (ref "U16") (pin "1") (pinfunction "VCC_1") (pintype "unspecified"))
      (node (ref "U19") (pin "1") (pinfunction "VCC_1") (pintype "unspecified"))
      (node (ref "U9") (pin "1") (pinfunction "VCC_1") (pintype "unspecified"))
    )
    (net (code "4") (name "GND") (class "Default")
      (node (ref "C1") (pin "1") (pinfunction "1_1") (pintype "unspecified"))
      (node (ref "C10") (pin "2") (pinfunction "2_2") (pintype "input"))
      (node (ref "C11") (pin "1") (pinfunction "1_1") (pintype "input"))
      (node (ref "C12") (pin "1") (pinfunction "1_1") (pintype "input"))
      (node (ref "C13") (pin "1") (pinfunction "1_1") (pintype "unspecified"))
      (node (ref "C14") (pin "2") (pinfunction "2_2") (pintype "input"))
      (node (ref "C16") (pin "1") (pinfunction "1_1") (pintype "input"))
      (node (ref "C17") (pin "2") (pinfunction "2_2") (pintype "input"))
      (node (ref "C19") (pin "1") (pinfunction "1_1") (pintype "input"))
      (node (ref "C2") (pin "1") (pinfunction "1_1") (pintype "unspecified"))
      (node (ref "C20") (pin "2") (pinfunction "2_2") (pintype "input"))
      (node (ref "C3") (pin "2") (pinfunction "2_2") (pintype "unspecified"))
      (node (ref "C4") (pin "1") (pinfunction "1_1") (pintype "input"))
      (node (ref "C5") (pin "2") (pinfunction "2_2") (pintype "input"))
      (node (ref "C7") (pin "1") (pinfunction "1_1") (pintype "input"))
      (node (ref "C8") (pin "2") (pinfunction "2_2") (pintype "input"))
      (node (ref "C9") (pin "2") (pinfunction "2_2") (pintype "input"))
      (node (ref "D2") (pin "2") (pinfunction "A_2") (pintype "unspecified"))
      (node (ref "R1") (pin "1") (pinfunction "1_1") (pintype "input"))
      (node (ref "R12") (pin "1") (pinfunction "1_1") (pintype "input"))
      (node (ref "R13") (pin "1") (pinfunction "1_1") (pintype "input"))
      (node (ref "SW1") (pin "1") (pinfunction "1_1") (pintype "input"))
      (node (ref "SW1") (pin "2") (pinfunction "2_2") (pintype "input"))
      (node (ref "SW2") (pin "1") (pinfunction "1_1") (pintype "input"))
      (node (ref "SW2") (pin "2") (pinfunction "2_2") (pintype "input"))
      (node (ref "SW3") (pin "1") (pinfunction "1_1") (pintype "input"))
      (node (ref "SW3") (pin "2") (pinfunction "2_2") (pintype "input"))
      (node (ref "SW4") (pin "1") (pinfunction "1_1") (pintype "input"))
      (node (ref "SW4") (pin "2") (pinfunction "2_2") (pintype "input"))
      (node (ref "U1") (pin "23") (pinfunction "VSS_23") (pintype "unspecified"))
      (node (ref "U1") (pin "47") (pinfunction "VSS_47") (pintype "unspecified"))
      (node (ref "U1") (pin "8") (pinfunction "VSSA_8") (pintype "unspecified"))
      (node (ref "U10") (pin "2") (pinfunction "SE_2") (pintype "unspecified"))
      (node (ref "U10") (pin "4") (pinfunction "GND_4") (pintype "unspecified"))
      (node (ref "U11") (pin "3") (pinfunction "GND_3") (pintype "unspecified"))
      (node (ref "U11") (pin "5") (pinfunction "ON/OFF_5") (pintype "unspecified"))
      (node (ref "U11") (pin "6") (pinfunction "GND_6") (pintype "unspecified"))
      (node (ref "U13") (pin "3") (pinfunction "VIN_3") (pintype "unspecified"))
      (node (ref "U15") (pin "3") (pinfunction "S_3") (pintype "input"))
      (node (ref "U16") (pin "4") (pinfunction "GND_4") (pintype "unspecified"))
      (node (ref "U18") (pin "3") (pinfunction "S_3") (pintype "input"))
      (node (ref "U19") (pin "4") (pinfunction "GND_4") (pintype "unspecified"))
      (node (ref "U2") (pin "2") (pinfunction "S_2") (pintype "unspecified"))
      (node (ref "U4") (pin "3") (pinfunction "S_3") (pintype "input"))
      (node (ref "U9") (pin "4") (pinfunction "GND_4") (pintype "unspecified"))
      (node (ref "X1") (pin "2") (pinfunction "2_2") (pintype "input"))
      (node (ref "X1") (pin "4") (pinfunction "4_4") (pintype "input"))
    )
    (net (code "5") (name "Net-(D1-K)") (class "Default")
      (node (ref "C6") (pin "2") (pinfunction "2_2") (pintype "unspecified"))
      (node (ref "D1") (pin "2") (pinfunction "K_2") (pintype "unspecified"))
      (node (ref "R7") (pin "1") (pinfunction "1_1") (pintype "input"))
      (node (ref "U9") (pin "7") (pinfunction "HO_7") (pintype "unspecified"))
      (node (ref "U9") (pin "8") (pinfunction "VB_8") (pintype "unspecified"))
    )
    (net (code "6") (name "Net-(D2-K)") (class "Default")
      (node (ref "D2") (pin "1") (pinfunction "K_1") (pintype "unspecified"))
      (node (ref "U11") (pin "2") (pinfunction "Output_2") (pintype "unspecified"))
      (node (ref "U12") (pin "1") (pinfunction "1_1") (pintype "unspecified"))
    )
    (net (code "7") (name "Net-(D3-A)") (class "Default")
      (node (ref "D3") (pin "2") (pinfunction "A_2") (pintype "unspecified"))
      (node (ref "L2") (pin "2") (pinfunction "2_2") (pintype "unspecified"))
      (node (ref "U10") (pin "1") (pinfunction "SC_1") (pintype "unspecified"))
    )
    (net (code "8") (name "Net-(D3-K)") (class "Default")
      (node (ref "D3") (pin "1") (pinfunction "K_1") (pintype "unspecified"))
      (node (ref "R11") (pin "2") (pinfunction "2_2") (pintype "input"))
    )
    (net (code "9") (name "Net-(D4-K)") (class "Default")
      (node (ref "C15") (pin "2") (pinfunction "2_2") (pintype "unspecified"))
      (node (ref "D4") (pin "2") (pinfunction "K_2") (pintype "unspecified"))
      (node (ref "R15") (pin "1") (pinfunction "1_1") (pintype "input"))
      (node (ref "U16") (pin "7") (pinfunction "HO_7") (pintype "unspecified"))
      (node (ref "U16") (pin "8") (pinfunction "VB_8") (pintype "unspecified"))
    )
    (net (code "10") (name "Net-(D5-K)") (class "Default")
      (node (ref "C18") (pin "2") (pinfunction "2_2") (pintype "unspecified"))
      (node (ref "D5") (pin "2") (pinfunction "K_2") (pintype "unspecified"))
      (node (ref "R17") (pin "1") (pinfunction "1_1") (pintype "input"))
      (node (ref "U19") (pin "7") (pinfunction "HO_7") (pintype "unspecified"))
      (node (ref "U19") (pin "8") (pinfunction "VB_8") (pintype "unspecified"))
    )
    (net (code "11") (name "Net-(L1-Pad1)") (class "Default")
      (node (ref "L1") (pin "1") (pinfunction "1_1") (pintype "unspecified"))
      (node (ref "R10") (pin "2") (pinfunction "2_2") (pintype "unspecified"))
      (node (ref "R8") (pin "2") (pinfunction "2_2") (pintype "input"))
      (node (ref "R9") (pin "2") (pinfunction "2_2") (pintype "unspecified"))
    )
    (net (code "12") (name "Net-(L1-Pad2)") (class "Default")
      (node (ref "L1") (pin "2") (pinfunction "2_2") (pintype "unspecified"))
      (node (ref "L2") (pin "1") (pinfunction "1_1") (pintype "unspecified"))
    )
    (net (code "13") (name "Net-(R2-Pad2)") (class "Default")
      (node (ref "R2") (pin "2") (pinfunction "2_2") (pintype "input"))
      (node (ref "SW1") (pin "3") (pinfunction "3_3") (pintype "input"))
      (node (ref "SW1") (pin "4") (pinfunction "4_4") (pintype "input"))
    )
    (net (code "14") (name "Net-(R3-Pad2)") (class "Default")
      (node (ref "R3") (pin "2") (pinfunction "2_2") (pintype "input"))
      (node (ref "SW2") (pin "3") (pinfunction "3_3") (pintype "input"))
      (node (ref "SW2") (pin "4") (pinfunction "4_4") (pintype "input"))
    )
    (net (code "15") (name "Net-(R4-Pad2)") (class "Default")
      (node (ref "R4") (pin "2") (pinfunction "2_2") (pintype "input"))
      (node (ref "SW3") (pin "3") (pinfunction "3_3") (pintype "input"))
      (node (ref "SW3") (pin "4") (pinfunction "4_4") (pintype "input"))
    )
    (net (code "16") (name "Net-(R5-Pad2)") (class "Default")
      (node (ref "R5") (pin "2") (pinfunction "2_2") (pintype "input"))
      (node (ref "SW4") (pin "3") (pinfunction "3_3") (pintype "input"))
      (node (ref "SW4") (pin "4") (pinfunction "4_4") (pintype "input"))
    )
    (net (code "17") (name "Net-(U1-BOOT0)") (class "Default")
      (node (ref "R1") (pin "2") (pinfunction "2_2") (pintype "input"))
      (node (ref "U1") (pin "44") (pinfunction "BOOT0_44") (pintype "unspecified"))
    )
    (net (code "18") (name "Net-(U1-PB6)") (class "Default")
      (node (ref "R5") (pin "1") (pinfunction "1_1") (pintype "input"))
      (node (ref "U1") (pin "42") (pinfunction "PB6_42") (pintype "unspecified"))
    )
    (net (code "19") (name "Net-(U1-PB7)") (class "Default")
      (node (ref "R4") (pin "1") (pinfunction "1_1") (pintype "input"))
      (node (ref "U1") (pin "43") (pinfunction "PB7_43") (pintype "unspecified"))
    )
    (net (code "20") (name "Net-(U1-PB8)") (class "Default")
      (node (ref "R3") (pin "1") (pinfunction "1_1") (pintype "input"))
      (node (ref "U1") (pin "45") (pinfunction "PB8_45") (pintype "unspecified"))
    )
    (net (code "21") (name "Net-(U1-PB9)") (class "Default")
      (node (ref "R2") (pin "1") (pinfunction "1_1") (pintype "input"))
      (node (ref "U1") (pin "46") (pinfunction "PB9_46") (pintype "unspecified"))
    )
    (net (code "22") (name "Net-(U1-PF0-OSC_IN)") (class "Default")
      (node (ref "C4") (pin "2") (pinfunction "2_2") (pintype "input"))
      (node (ref "U1") (pin "5") (pinfunction "PF0-OSC_IN_5") (pintype "unspecified"))
      (node (ref "X1") (pin "3") (pinfunction "3_3") (pintype "input"))
    )
    (net (code "23") (name "Net-(U1-PF1-OSC_OUT)") (class "Default")
      (node (ref "C5") (pin "1") (pinfunction "1_1") (pintype "input"))
      (node (ref "U1") (pin "6") (pinfunction "PF1-OSC_OUT_6") (pintype "unspecified"))
      (node (ref "X1") (pin "1") (pinfunction "1_1") (pintype "input"))
    )
    (net (code "24") (name "Net-(U2-D)") (class "Default")
      (node (ref "H8") (pin "1") (pinfunction "1_1") (pintype "unspecified"))
      (node (ref "U2") (pin "3") (pinfunction "D_3") (pintype "unspecified"))
    )
    (net (code "25") (name "Net-(U3-G)") (class "Default")
      (node (ref "R7") (pin "2") (pinfunction "2_2") (pintype "input"))
      (node (ref "U3") (pin "1") (pinfunction "G_1") (pintype "input"))
    )
    (net (code "26") (name "Net-(U3-S)") (class "Default")
      (node (ref "C6") (pin "1") (pinfunction "1_1") (pintype "unspecified"))
      (node (ref "TP2") (pin "1") (pinfunction "1_1") (pintype "input"))
      (node (ref "U3") (pin "3") (pinfunction "S_3") (pintype "input"))
      (node (ref "U4") (pin "2") (pinfunction "D_2") (pintype "input"))
      (node (ref "U9") (pin "6") (pinfunction "VS_6") (pintype "unspecified"))
    )
    (net (code "27") (name "Net-(U4-G)") (class "Default")
      (node (ref "R6") (pin "2") (pinfunction "2_2") (pintype "input"))
      (node (ref "U4") (pin "1") (pinfunction "G_1") (pintype "input"))
    )
    (net (code "28") (name "Net-(U9-LO)") (class "Default")
      (node (ref "R6") (pin "1") (pinfunction "1_1") (pintype "input"))
      (node (ref "U9") (pin "5") (pinfunction "LO_5") (pintype "unspecified"))
    )
    (net (code "29") (name "Net-(U10-CT)") (class "Default")
      (node (ref "C10") (pin "1") (pinfunction "1_1") (pintype "input"))
      (node (ref "U10") (pin "3") (pinfunction "CT_3") (pintype "unspecified"))
    )
    (net (code "30") (name "Net-(U10-DC)") (class "Default")
      (node (ref "R8") (pin "1") (pinfunction "1_1") (pintype "input"))
      (node (ref "U10") (pin "8") (pinfunction "DC_8") (pintype "unspecified"))
    )
    (net (code "31") (name "Net-(U10-IPK)") (class "Default")
      (node (ref "R10") (pin "1") (pinfunction "1_1") (pintype "unspecified"))
      (node (ref "R9") (pin "1") (pinfunction "1_1") (pintype "unspecified"))
      (node (ref "U10") (pin "7") (pinfunction "IPK_7") (pintype "unspecified"))
    )
    (net (code "32") (name "Net-(U14-G)") (class "Default")
      (node (ref "R15") (pin "2") (pinfunction "2_2") (pintype "input"))
      (node (ref "U14") (pin "1") (pinfunction "G_1") (pintype "input"))
    )
    (net (code "33") (name "Net-(U14-S)") (class "Default")
      (node (ref "C15") (pin "1") (pinfunction "1_1") (pintype "unspecified"))
      (node (ref "TP3") (pin "1") (pinfunction "1_1") (pintype "input"))
      (node (ref "U14") (pin "3") (pinfunction "S_3") (pintype "input"))
      (node (ref "U15") (pin "2") (pinfunction "D_2") (pintype "input"))
      (node (ref "U16") (pin "6") (pinfunction "VS_6") (pintype "unspecified"))
    )
    (net (code "34") (name "Net-(U15-G)") (class "Default")
      (node (ref "R14") (pin "2") (pinfunction "2_2") (pintype "input"))
      (node (ref "U15") (pin "1") (pinfunction "G_1") (pintype "input"))
    )
    (net (code "35") (name "Net-(U16-LO)") (class "Default")
      (node (ref "R14") (pin "1") (pinfunction "1_1") (pintype "input"))
      (node (ref "U16") (pin "5") (pinfunction "LO_5") (pintype "unspecified"))
    )
    (net (code "36") (name "Net-(U17-G)") (class "Default")
      (node (ref "R17") (pin "2") (pinfunction "2_2") (pintype "input"))
      (node (ref "U17") (pin "1") (pinfunction "G_1") (pintype "input"))
    )
    (net (code "37") (name "Net-(U17-S)") (class "Default")
      (node (ref "C18") (pin "1") (pinfunction "1_1") (pintype "unspecified"))
      (node (ref "TP1") (pin "1") (pinfunction "1_1") (pintype "input"))
      (node (ref "U17") (pin "3") (pinfunction "S_3") (pintype "input"))
      (node (ref "U18") (pin "2") (pinfunction "D_2") (pintype "input"))
      (node (ref "U19") (pin "6") (pinfunction "VS_6") (pintype "unspecified"))
    )
    (net (code "38") (name "Net-(U18-G)") (class "Default")
      (node (ref "R16") (pin "2") (pinfunction "2_2") (pintype "input"))
      (node (ref "U18") (pin "1") (pinfunction "G_1") (pintype "input"))
    )
    (net (code "39") (name "Net-(U19-LO)") (class "Default")
      (node (ref "R16") (pin "1") (pinfunction "1_1") (pintype "input"))
      (node (ref "U19") (pin "5") (pinfunction "LO_5") (pintype "unspecified"))
    )
    (net (code "40") (name "PA0_XUAN_BIAN_TIAO0") (class "Default")
      (node (ref "H3") (pin "1") (pinfunction "1_1") (pintype "unspecified"))
    )
    (net (code "41") (name "PA1_SPI2_MOSI") (class "Default")
      (node (ref "H4") (pin "1") (pinfunction "1_1") (pintype "unspecified"))
    )
    (net (code "42") (name "PA2_SPI2_SCK") (class "Default")
      (node (ref "H5") (pin "1") (pinfunction "1_1") (pintype "unspecified"))
    )
    (net (code "43") (name "PA3_SPI2_CS") (class "Default")
      (node (ref "H6") (pin "1") (pinfunction "1_1") (pintype "unspecified"))
    )
    (net (code "44") (name "PA8_ATIM_CH1A_U_H") (class "Default")
      (node (ref "U1") (pin "29") (pinfunction "PA8_29") (pintype "unspecified"))
      (node (ref "U9") (pin "2") (pinfunction "HIN_2") (pintype "unspecified"))
    )
    (net (code "45") (name "PA9_ATIM_CH2A_U_H") (class "Default")
      (node (ref "U16") (pin "2") (pinfunction "HIN_2") (pintype "unspecified"))
    )
    (net (code "46") (name "PA9_ATIM_CH2A_V_H") (class "Default")
      (node (ref "U1") (pin "30") (pinfunction "PA9_30") (pintype "unspecified"))
    )
    (net (code "47") (name "PA10_ATIM_CH3A_U_H") (class "Default")
      (node (ref "U19") (pin "2") (pinfunction "HIN_2") (pintype "unspecified"))
    )
    (net (code "48") (name "PA10_ATIM_CH3A_W_H") (class "Default")
      (node (ref "U1") (pin "31") (pinfunction "PA10_31") (pintype "unspecified"))
    )
    (net (code "49") (name "PA13_SWDIO") (class "Default")
      (node (ref "H2") (pin "1") (pinfunction "1_1") (pintype "unspecified"))
      (node (ref "U1") (pin "34") (pinfunction "PA13_34") (pintype "unspecified"))
    )
    (net (code "50") (name "PA14_SWCLK") (class "Default")
      (node (ref "H1") (pin "1") (pinfunction "1_1") (pintype "unspecified"))
      (node (ref "U1") (pin "37") (pinfunction "PA14_37") (pintype "unspecified"))
    )
    (net (code "51") (name "PA15_SPI1_CS_LCD_A0") (class "Default")
      (node (ref "U1") (pin "38") (pinfunction "PA15_38") (pintype "unspecified"))
    )
    (net (code "52") (name "PB3_SPI1_SCK") (class "Default")
      (node (ref "U1") (pin "39") (pinfunction "PB3_39") (pintype "unspecified"))
    )
    (net (code "53") (name "PB4_LCD_RST") (class "Default")
      (node (ref "U1") (pin "40") (pinfunction "PB4_40") (pintype "unspecified"))
    )
    (net (code "54") (name "PB5_SPI1_MOSI") (class "Default")
      (node (ref "U1") (pin "41") (pinfunction "PB5_41") (pintype "unspecified"))
    )
    (net (code "55") (name "PB12_ATIM_BK") (class "Default")
      (node (ref "U1") (pin "25") (pinfunction "PB12_25") (pintype "unspecified"))
    )
    (net (code "56") (name "PB13_ATIM_CH1B_U_L") (class "Default")
      (node (ref "U1") (pin "26") (pinfunction "PB13_26") (pintype "unspecified"))
      (node (ref "U9") (pin "3") (pinfunction "LIN_3") (pintype "unspecified"))
    )
    (net (code "57") (name "PB14_ATIM_CH2B_U_L") (class "Default")
      (node (ref "U16") (pin "3") (pinfunction "LIN_3") (pintype "unspecified"))
    )
    (net (code "58") (name "PB14_ATIM_CH2B_V_L") (class "Default")
      (node (ref "U1") (pin "27") (pinfunction "PB14_27") (pintype "unspecified"))
    )
    (net (code "59") (name "PB15_ATIM_CH3B_U_L") (class "Default")
      (node (ref "U19") (pin "3") (pinfunction "LIN_3") (pintype "unspecified"))
    )
    (net (code "60") (name "PB15_ATIM_CH3B_W_L") (class "Default")
      (node (ref "U1") (pin "28") (pinfunction "PB15_28") (pintype "unspecified"))
    )
    (net (code "61") (name "VCC") (class "Default")
      (node (ref "C14") (pin "1") (pinfunction "1_1") (pintype "input"))
      (node (ref "C17") (pin "1") (pinfunction "1_1") (pintype "input"))
      (node (ref "C20") (pin "1") (pinfunction "1_1") (pintype "input"))
      (node (ref "C8") (pin "1") (pinfunction "1_1") (pintype "input"))
      (node (ref "U11") (pin "1") (pinfunction "Vin_1") (pintype "unspecified"))
      (node (ref "U14") (pin "2") (pinfunction "D_2") (pintype "input"))
      (node (ref "U17") (pin "2") (pinfunction "D_2") (pintype "input"))
      (node (ref "U3") (pin "2") (pinfunction "D_2") (pintype "input"))
    )
    (net (code "63") (name "unconnected-(U1-NRST-Pad7)") (class "Default")
      (node (ref "U1") (pin "7") (pinfunction "NRST_7") (pintype "unspecified"))
    )
    (net (code "64") (name "unconnected-(U1-PA0-Pad10)") (class "Default")
      (node (ref "U1") (pin "10") (pinfunction "PA0_10") (pintype "unspecified"))
    )
    (net (code "65") (name "unconnected-(U1-PA1-Pad11)") (class "Default")
      (node (ref "U1") (pin "11") (pinfunction "PA1_11") (pintype "unspecified"))
    )
    (net (code "66") (name "unconnected-(U1-PA2-Pad12)") (class "Default")
      (node (ref "U1") (pin "12") (pinfunction "PA2_12") (pintype "unspecified"))
    )
    (net (code "67") (name "unconnected-(U1-PA3-Pad13)") (class "Default")
      (node (ref "U1") (pin "13") (pinfunction "PA3_13") (pintype "unspecified"))
    )
    (net (code "68") (name "unconnected-(U1-PA4-Pad14)") (class "Default")
      (node (ref "U1") (pin "14") (pinfunction "PA4_14") (pintype "unspecified"))
    )
    (net (code "69") (name "unconnected-(U1-PA5-Pad15)") (class "Default")
      (node (ref "U1") (pin "15") (pinfunction "PA5_15") (pintype "unspecified"))
    )
    (net (code "70") (name "unconnected-(U1-PA6-Pad16)") (class "Default")
      (node (ref "U1") (pin "16") (pinfunction "PA6_16") (pintype "unspecified"))
    )
    (net (code "71") (name "unconnected-(U1-PA7-Pad17)") (class "Default")
      (node (ref "U1") (pin "17") (pinfunction "PA7_17") (pintype "unspecified"))
    )
    (net (code "72") (name "unconnected-(U1-PA11-Pad32)") (class "Default")
      (node (ref "U1") (pin "32") (pinfunction "PA11_32") (pintype "unspecified"))
    )
    (net (code "73") (name "unconnected-(U1-PA12-Pad33)") (class "Default")
      (node (ref "U1") (pin "33") (pinfunction "PA12_33") (pintype "unspecified"))
    )
    (net (code "74") (name "unconnected-(U1-PB0-Pad18)") (class "Default")
      (node (ref "U1") (pin "18") (pinfunction "PB0_18") (pintype "unspecified"))
    )
    (net (code "75") (name "unconnected-(U1-PB1-Pad19)") (class "Default")
      (node (ref "U1") (pin "19") (pinfunction "PB1_19") (pintype "unspecified"))
    )
    (net (code "76") (name "unconnected-(U1-PB2-Pad20)") (class "Default")
      (node (ref "U1") (pin "20") (pinfunction "PB2_20") (pintype "unspecified"))
    )
    (net (code "77") (name "unconnected-(U1-PB10-Pad21)") (class "Default")
      (node (ref "U1") (pin "21") (pinfunction "PB10_21") (pintype "unspecified"))
    )
    (net (code "78") (name "unconnected-(U1-PB11-Pad22)") (class "Default")
      (node (ref "U1") (pin "22") (pinfunction "PB11_22") (pintype "unspecified"))
    )
    (net (code "79") (name "unconnected-(U1-PC13-Pad2)") (class "Default")
      (node (ref "U1") (pin "2") (pinfunction "PC13_2") (pintype "unspecified"))
    )
    (net (code "80") (name "unconnected-(U1-PC14-OSC32_IN-Pad3)") (class "Default")
      (node (ref "U1") (pin "3") (pinfunction "PC14-OSC32_IN_3") (pintype "unspecified"))
    )
    (net (code "81") (name "unconnected-(U1-PC15-OSC32_OUT-Pad4)") (class "Default")
      (node (ref "U1") (pin "4") (pinfunction "PC15-OSC32_OUT_4") (pintype "unspecified"))
    )
    (net (code "82") (name "unconnected-(U1-PF6-Pad35)") (class "Default")
      (node (ref "U1") (pin "35") (pinfunction "PF6_35") (pintype "unspecified"))
    )
    (net (code "83") (name "unconnected-(U1-PF7-Pad36)") (class "Default")
      (node (ref "U1") (pin "36") (pinfunction "PF7_36") (pintype "unspecified"))
    )
    (net (code "84") (name "unconnected-(U2-G-Pad1)") (class "Default")
      (node (ref "U2") (pin "1") (pinfunction "G_1") (pintype "unspecified"))
    )
  )
)
